# pbalduino.net
KiCad netlist of a schematic drawn in EAGLE
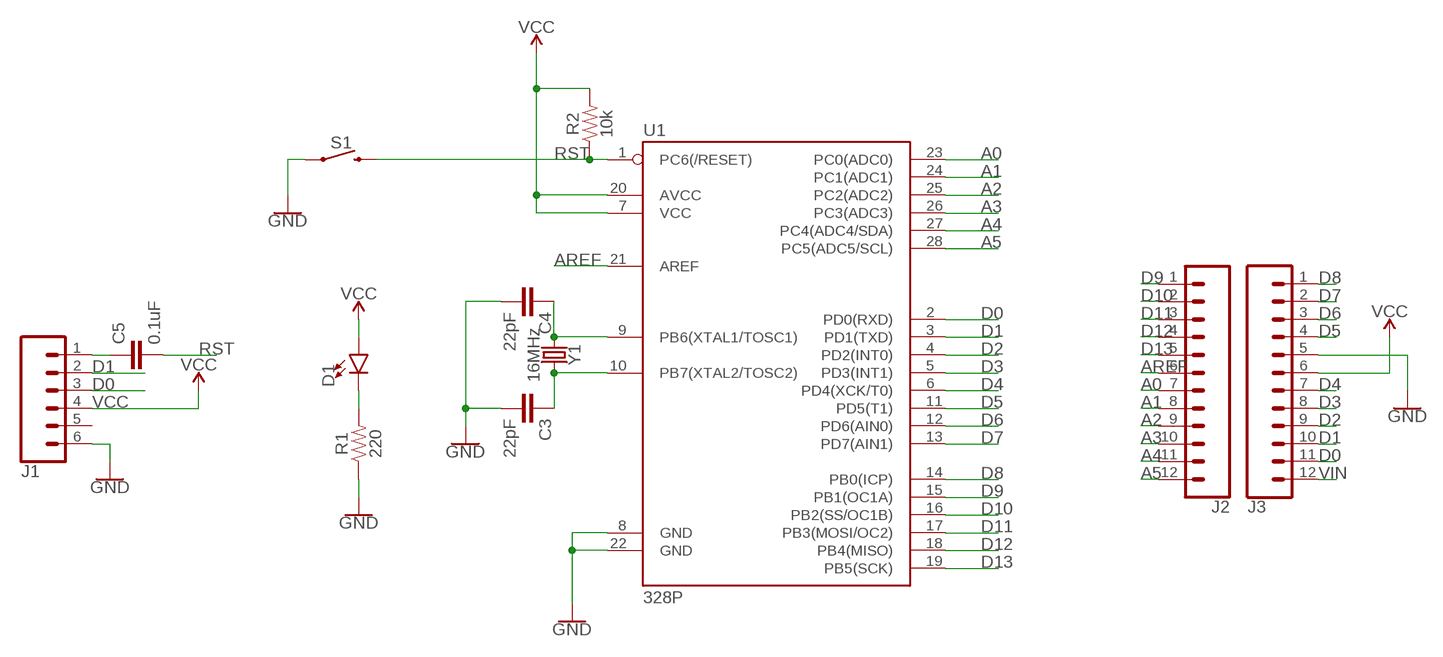
[diagram p0: schematic, sheet 1]

(export (version "E")
  (design (tool "Eeschema 10.0.6"))
  (components
    (comp (ref "C3")
      (value "22pF")
      (footprint "eagle-import:CAP-PTH-2.54")
      (libsource (lib "eagle-import") (part "22PF-PTH-2.54MM-200V-5%"))
    )
    (comp (ref "C4")
      (value "22pF")
      (footprint "eagle-import:CAP-PTH-2.54")
      (libsource (lib "eagle-import") (part "22PF-PTH-2.54MM-200V-5%"))
    )
    (comp (ref "C5")
      (value "0.1uF")
      (footprint "eagle-import:CAP-PTH-SMALL-KIT")
      (libsource (lib "eagle-import") (part "0.1UF-KIT-EZ-50V-20%"))
    )
    (comp (ref "D1")
      (value "LED-3MM-NO_SILK")
      (footprint "eagle-import:LED_3MM-NS")
      (libsource (lib "eagle-import") (part "LED-3MM-NO_SILK"))
    )
    (comp (ref "J1")
      (value "CONN_06LOCK")
      (footprint "eagle-import:1X06_LOCK")
      (libsource (lib "eagle-import") (part "CONN_06LOCK"))
    )
    (comp (ref "J2")
      (value "CONN_12")
      (footprint "eagle-import:1X12")
      (libsource (lib "eagle-import") (part "CONN_12"))
    )
    (comp (ref "J3")
      (value "CONN_12")
      (footprint "eagle-import:1X12")
      (libsource (lib "eagle-import") (part "CONN_12"))
    )
    (comp (ref "R1")
      (value "220")
      (footprint "eagle-import:AXIAL-0.1")
      (libsource (lib "eagle-import") (part "1KOHM-VERT-1/4W-5%"))
    )
    (comp (ref "R2")
      (value "10k")
      (footprint "eagle-import:AXIAL-0.1")
      (libsource (lib "eagle-import") (part "1KOHM-VERT-1/4W-5%"))
    )
    (comp (ref "S1")
      (value "MOMENTARY-SWITCH-SPST-PTH-6.0MM")
      (footprint "eagle-import:TACTILE_SWITCH_PTH_6.0MM")
      (libsource (lib "eagle-import") (part "MOMENTARY-SWITCH-SPST-PTH-6.0MM"))
    )
    (comp (ref "U1")
      (value "328P")
      (footprint "eagle-import:DIP28")
      (libsource (lib "eagle-import") (part "ATMEGA328P_PDIP"))
    )
    (comp (ref "Y1")
      (value "16MHz")
      (footprint "eagle-import:HC49US")
      (libsource (lib "eagle-import") (part "CRYSTAL-16MHZPTH-HC49US"))
    )
  )
  (nets
    (net (code "1") (name "/A0") (class "Default")
      (node (ref "J2") (pin "7") (pinfunction "7_7") (pintype "passive"))
      (node (ref "U1") (pin "23") (pinfunction "PC0(ADC0)_23") (pintype "bidirectional"))
    )
    (net (code "2") (name "/A1") (class "Default")
      (node (ref "J2") (pin "8") (pinfunction "8_8") (pintype "passive"))
      (node (ref "U1") (pin "24") (pinfunction "PC1(ADC1)_24") (pintype "bidirectional"))
    )
    (net (code "3") (name "/A2") (class "Default")
      (node (ref "J2") (pin "9") (pinfunction "9_9") (pintype "passive"))
      (node (ref "U1") (pin "25") (pinfunction "PC2(ADC2)_25") (pintype "bidirectional"))
    )
    (net (code "4") (name "/A3") (class "Default")
      (node (ref "J2") (pin "10") (pinfunction "10_10") (pintype "passive"))
      (node (ref "U1") (pin "26") (pinfunction "PC3(ADC3)_26") (pintype "bidirectional"))
    )
    (net (code "5") (name "/A4") (class "Default")
      (node (ref "J2") (pin "11") (pinfunction "11_11") (pintype "passive"))
      (node (ref "U1") (pin "27") (pinfunction "PC4(ADC4/SDA)_27") (pintype "bidirectional"))
    )
    (net (code "6") (name "/A5") (class "Default")
      (node (ref "J2") (pin "12") (pinfunction "12_12") (pintype "passive"))
      (node (ref "U1") (pin "28") (pinfunction "PC5(ADC5/SCL)_28") (pintype "bidirectional"))
    )
    (net (code "7") (name "/AREF") (class "Default")
      (node (ref "J2") (pin "6") (pinfunction "6_6") (pintype "passive"))
      (node (ref "U1") (pin "21") (pinfunction "AREF_21") (pintype "bidirectional"))
    )
    (net (code "8") (name "/D0") (class "Default")
      (node (ref "J1") (pin "3") (pinfunction "3_3") (pintype "passive"))
      (node (ref "J3") (pin "11") (pinfunction "11_11") (pintype "passive"))
      (node (ref "U1") (pin "2") (pinfunction "PD0(RXD)_2") (pintype "bidirectional"))
    )
    (net (code "9") (name "/D1") (class "Default")
      (node (ref "J1") (pin "2") (pinfunction "2_2") (pintype "passive"))
      (node (ref "J3") (pin "10") (pinfunction "10_10") (pintype "passive"))
      (node (ref "U1") (pin "3") (pinfunction "PD1(TXD)_3") (pintype "bidirectional"))
    )
    (net (code "10") (name "/D2") (class "Default")
      (node (ref "J3") (pin "9") (pinfunction "9_9") (pintype "passive"))
      (node (ref "U1") (pin "4") (pinfunction "PD2(INT0)_4") (pintype "bidirectional"))
    )
    (net (code "11") (name "/D3") (class "Default")
      (node (ref "J3") (pin "8") (pinfunction "8_8") (pintype "passive"))
      (node (ref "U1") (pin "5") (pinfunction "PD3(INT1)_5") (pintype "bidirectional"))
    )
    (net (code "12") (name "/D4") (class "Default")
      (node (ref "J3") (pin "7") (pinfunction "7_7") (pintype "passive"))
      (node (ref "U1") (pin "6") (pinfunction "PD4(XCK/T0)_6") (pintype "bidirectional"))
    )
    (net (code "13") (name "/D5") (class "Default")
      (node (ref "J3") (pin "4") (pinfunction "4_4") (pintype "passive"))
      (node (ref "U1") (pin "11") (pinfunction "PD5(T1)_11") (pintype "bidirectional"))
    )
    (net (code "14") (name "/D6") (class "Default")
      (node (ref "J3") (pin "3") (pinfunction "3_3") (pintype "passive"))
      (node (ref "U1") (pin "12") (pinfunction "PD6(AIN0)_12") (pintype "bidirectional"))
    )
    (net (code "15") (name "/D7") (class "Default")
      (node (ref "J3") (pin "2") (pinfunction "2_2") (pintype "passive"))
      (node (ref "U1") (pin "13") (pinfunction "PD7(AIN1)_13") (pintype "bidirectional"))
    )
    (net (code "16") (name "/D8") (class "Default")
      (node (ref "J3") (pin "1") (pinfunction "1_1") (pintype "passive"))
      (node (ref "U1") (pin "14") (pinfunction "PB0(ICP)_14") (pintype "bidirectional"))
    )
    (net (code "17") (name "/D9") (class "Default")
      (node (ref "J2") (pin "1") (pinfunction "1_1") (pintype "passive"))
      (node (ref "U1") (pin "15") (pinfunction "PB1(OC1A)_15") (pintype "bidirectional"))
    )
    (net (code "18") (name "/D10") (class "Default")
      (node (ref "J2") (pin "2") (pinfunction "2_2") (pintype "passive"))
      (node (ref "U1") (pin "16") (pinfunction "PB2(SS/OC1B)_16") (pintype "bidirectional"))
    )
    (net (code "19") (name "/D11") (class "Default")
      (node (ref "J2") (pin "3") (pinfunction "3_3") (pintype "passive"))
      (node (ref "U1") (pin "17") (pinfunction "PB3(MOSI/OC2)_17") (pintype "bidirectional"))
    )
    (net (code "20") (name "/D12") (class "Default")
      (node (ref "J2") (pin "4") (pinfunction "4_4") (pintype "passive"))
      (node (ref "U1") (pin "18") (pinfunction "PB4(MISO)_18") (pintype "bidirectional"))
    )
    (net (code "21") (name "/D13") (class "Default")
      (node (ref "J2") (pin "5") (pinfunction "5_5") (pintype "passive"))
      (node (ref "U1") (pin "19") (pinfunction "PB5(SCK)_19") (pintype "bidirectional"))
    )
    (net (code "22") (name "/RST") (class "Default")
      (node (ref "C5") (pin "2") (pinfunction "2_2") (pintype "passive"))
      (node (ref "R2") (pin "P$1") (pinfunction "1_P$1") (pintype "passive"))
      (node (ref "S1") (pin "3") (pinfunction "2_3") (pintype "passive"))
      (node (ref "U1") (pin "1") (pinfunction "PC6(/RESET)_1") (pintype "bidirectional"))
    )
    (net (code "23") (name "/VIN") (class "Default")
      (node (ref "J3") (pin "12") (pinfunction "12_12") (pintype "passive"))
    )
    (net (code "24") (name "GND") (class "Default")
      (node (ref "C3") (pin "2") (pinfunction "2_2") (pintype "passive"))
      (node (ref "C4") (pin "2") (pinfunction "2_2") (pintype "passive"))
      (node (ref "J1") (pin "6") (pinfunction "6_6") (pintype "passive"))
      (node (ref "J3") (pin "5") (pinfunction "5_5") (pintype "passive"))
      (node (ref "R1") (pin "P$1") (pinfunction "1_P$1") (pintype "passive"))
      (node (ref "S1") (pin "1") (pinfunction "1_1") (pintype "passive"))
      (node (ref "U1") (pin "22") (pinfunction "GND_22") (pintype "bidirectional"))
      (node (ref "U1") (pin "8") (pinfunction "GND_8") (pintype "bidirectional"))
    )
    (net (code "25") (name "Net-(C5-Pad1)") (class "Default")
      (node (ref "C5") (pin "1") (pinfunction "1_1") (pintype "passive"))
      (node (ref "J1") (pin "1") (pinfunction "1_1") (pintype "passive"))
    )
    (net (code "26") (name "Net-(D1-C)") (class "Default")
      (node (ref "D1") (pin "K") (pinfunction "C_K") (pintype "passive"))
      (node (ref "R1") (pin "P$2") (pinfunction "2_P$2") (pintype "passive"))
    )
    (net (code "27") (name "Net-(U1-PB6(XTAL1{slash}TOSC1))") (class "Default")
      (node (ref "C4") (pin "1") (pinfunction "1_1") (pintype "passive"))
      (node (ref "U1") (pin "9") (pinfunction "PB6(XTAL1/TOSC1)_9") (pintype "bidirectional"))
      (node (ref "Y1") (pin "1") (pinfunction "1_1") (pintype "passive"))
    )
    (net (code "28") (name "Net-(U1-PB7(XTAL2{slash}TOSC2))") (class "Default")
      (node (ref "C3") (pin "1") (pinfunction "1_1") (pintype "passive"))
      (node (ref "U1") (pin "10") (pinfunction "PB7(XTAL2/TOSC2)_10") (pintype "bidirectional"))
      (node (ref "Y1") (pin "2") (pinfunction "2_2") (pintype "passive"))
    )
    (net (code "29") (name "VCC") (class "Default")
      (node (ref "D1") (pin "A") (pinfunction "A_A") (pintype "passive"))
      (node (ref "J1") (pin "4") (pinfunction "4_4") (pintype "passive"))
      (node (ref "J3") (pin "6") (pinfunction "6_6") (pintype "passive"))
      (node (ref "R2") (pin "P$2") (pinfunction "2_P$2") (pintype "passive"))
      (node (ref "U1") (pin "20") (pinfunction "AVCC_20") (pintype "bidirectional"))
      (node (ref "U1") (pin "7") (pinfunction "VCC_7") (pintype "bidirectional"))
    )
    (net (code "30") (name "unconnected-(J1-Pad5)") (class "Default")
      (node (ref "J1") (pin "5") (pinfunction "5_5") (pintype "passive"))
    )
  )
)
